# INT_REG.net
KiCad netlist of a schematic drawn in Altium Designer
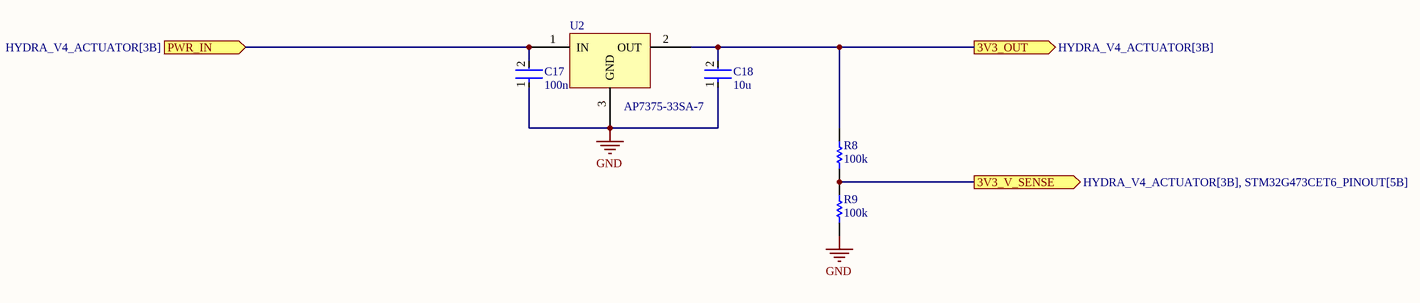
[diagram p0: INT_REG.SchDoc]

(export (version "E")
  (design (tool "Eeschema 10.0.6"))
  (components
    (comp (ref "C17")
      (value "100n")
      (footprint "FP-0402-L_1_0_0_05-W_0_5-IPC_A")
      (description "LARGE PADS, 0402 CAP, CHANGE COMMENT TO MATCH REAL P/N")
      (libsource (lib "Space Concordia") (part "b4654b650e69147ec39a6b967a45e02"))
    )
    (comp (ref "C18")
      (value "10u")
      (footprint "FP-0402-L_1_0_0_05-W_0_5-IPC_A")
      (description "LARGE PADS, 0402 CAP, CHANGE COMMENT TO MATCH REAL P/N")
      (libsource (lib "Space Concordia") (part "b4654b650e69147ec39a6b967a45e02"))
    )
    (comp (ref "R8")
      (value "100k")
      (footprint "R0603B")
      (description "Resistor")
      (libsource (lib "Space Concordia") (part "Resistor"))
    )
    (comp (ref "R9")
      (value "100k")
      (footprint "R0603B")
      (description "Resistor")
      (libsource (lib "Space Concordia") (part "Resistor"))
    )
    (comp (ref "U2")
      (value "AP7375-33SA-7")
      (footprint "SOT90P285X110-3N")
      (description "LDO Regulator Pos 3.3V 0.3A 3-Pin SOT-23 T/R")
      (libsource (lib "Space Concordia") (part "AP7375-33SA-7"))
    )
  )
  (nets
    (net (code "1") (name "/3V3_OUT") (class "Default")
      (node (ref "C18") (pin "2") (pinfunction "2_2") (pintype "passive"))
      (node (ref "R8") (pin "2") (pinfunction "2_2") (pintype "passive"))
      (node (ref "U2") (pin "2") (pinfunction "OUT_2") (pintype "passive"))
    )
    (net (code "2") (name "/3V3_V_SENSE") (class "Default")
      (node (ref "R8") (pin "1") (pinfunction "1_1") (pintype "passive"))
      (node (ref "R9") (pin "2") (pinfunction "2_2") (pintype "passive"))
    )
    (net (code "3") (name "/PWR_IN") (class "Default")
      (node (ref "C17") (pin "2") (pinfunction "2_2") (pintype "passive"))
      (node (ref "U2") (pin "1") (pinfunction "IN_1") (pintype "passive"))
    )
    (net (code "4") (name "GND") (class "Default")
      (node (ref "C17") (pin "1") (pinfunction "1_1") (pintype "passive"))
      (node (ref "C18") (pin "1") (pinfunction "1_1") (pintype "passive"))
      (node (ref "R9") (pin "1") (pinfunction "1_1") (pintype "passive"))
      (node (ref "U2") (pin "3") (pinfunction "GND_3") (pintype "passive"))
    )
  )
)
